# flatlamp.net
KiCad netlist of a schematic drawn in EAGLE
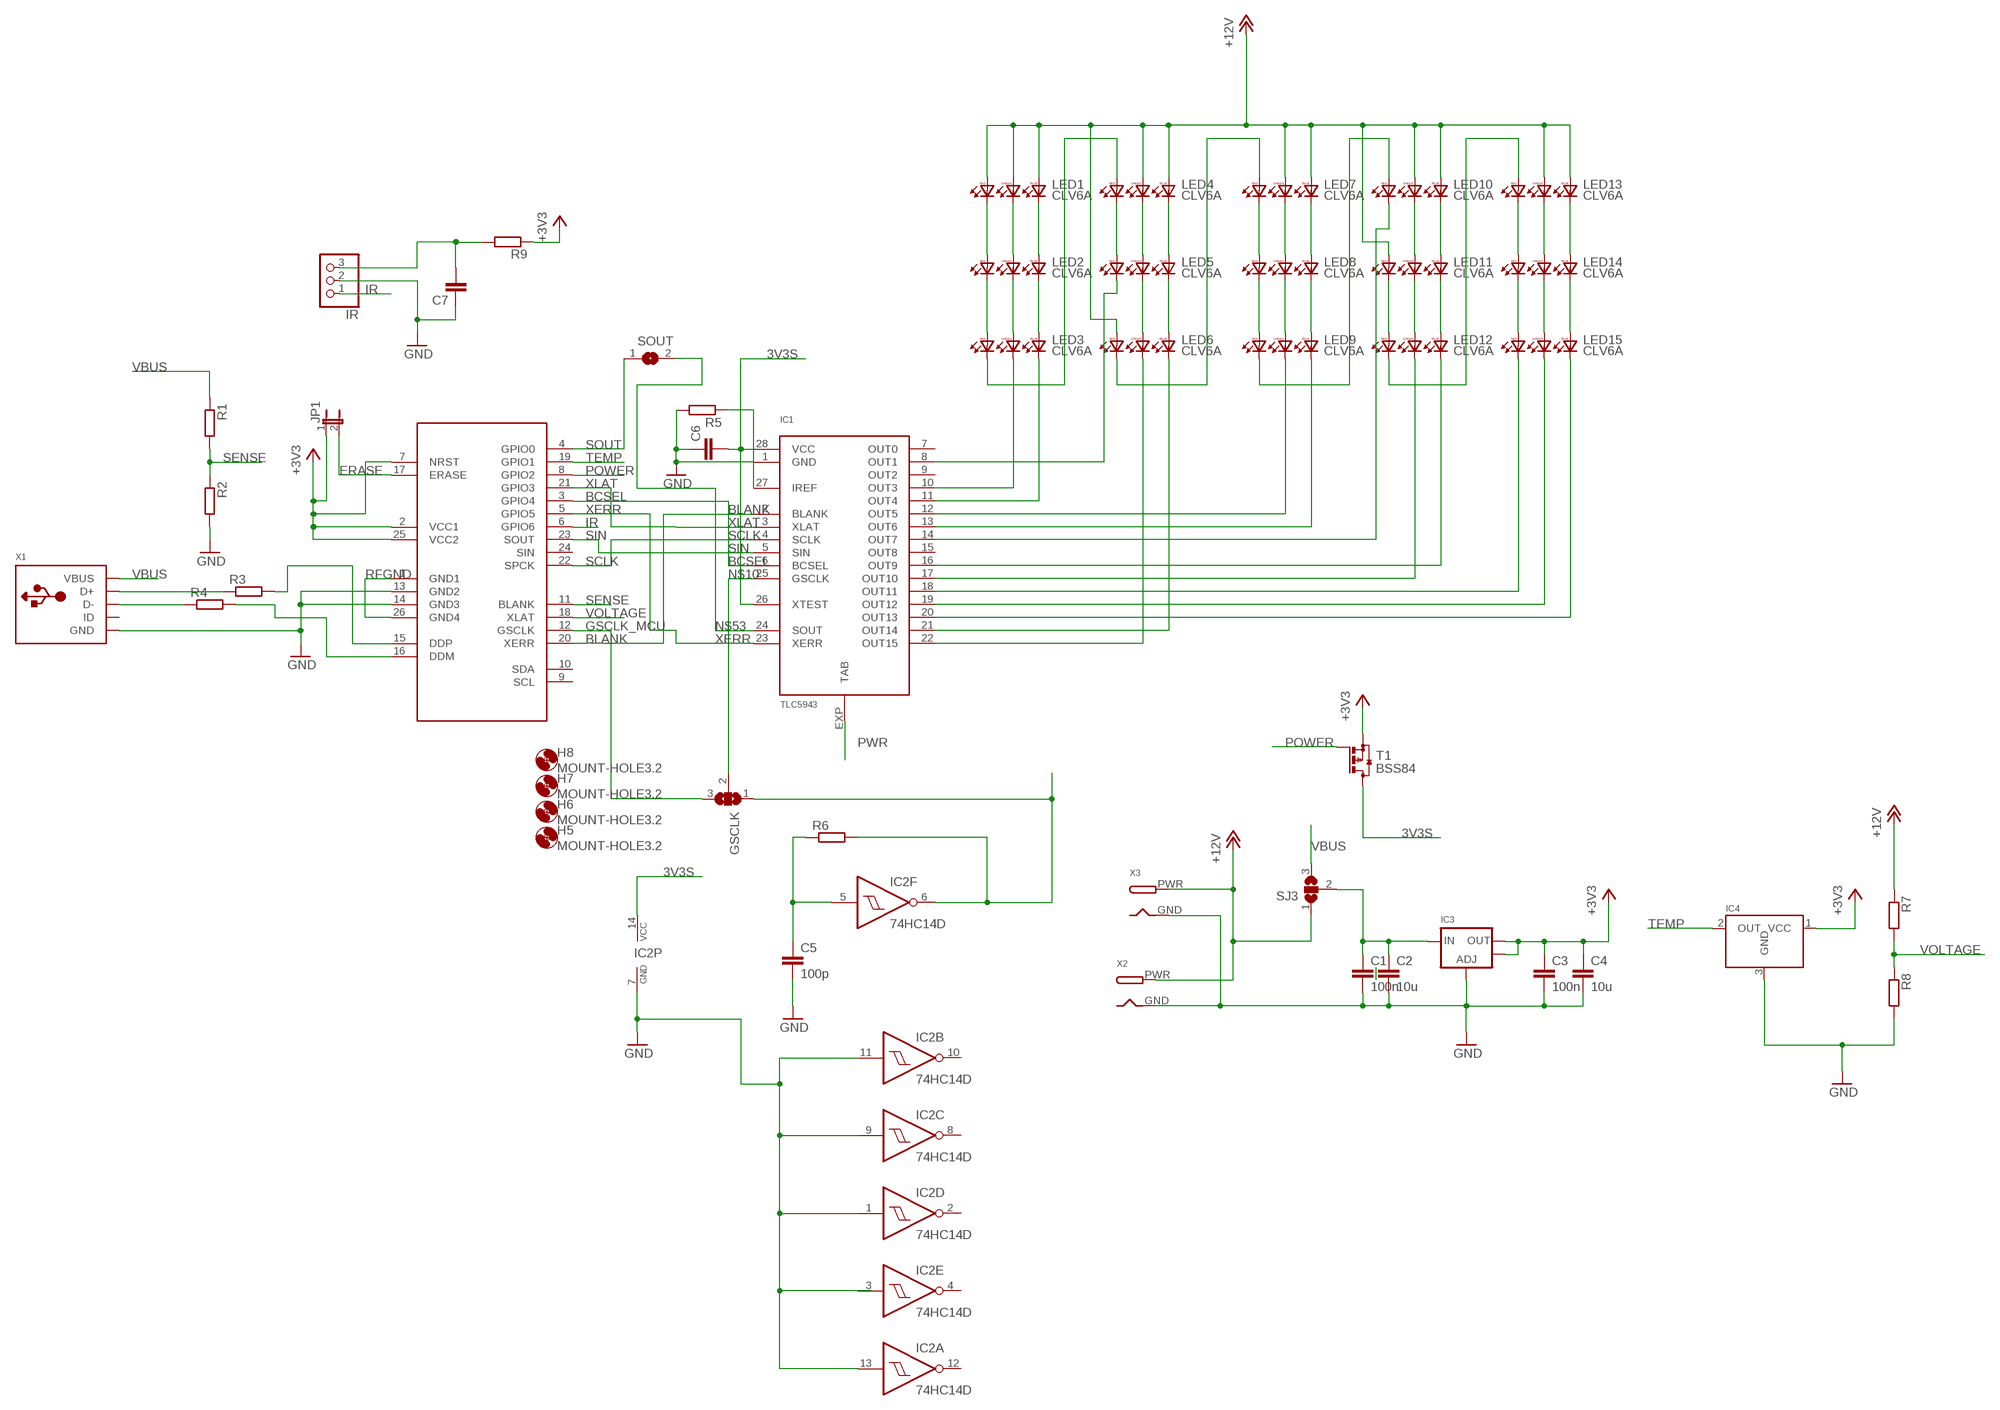
[diagram p0: schematic, sheet 1]

(export (version "E")
  (design (tool "Eeschema 10.0.6"))
  (components
    (comp (ref "C1")
      (value "100n")
      (footprint "eagle-import:C0805")
      (libsource (lib "eagle-import") (part "C-EUC0805"))
    )
    (comp (ref "C2")
      (value "10u")
      (footprint "eagle-import:C0805")
      (libsource (lib "eagle-import") (part "C-EUC0805"))
    )
    (comp (ref "C3")
      (value "100n")
      (footprint "eagle-import:C0805")
      (libsource (lib "eagle-import") (part "C-EUC0805"))
    )
    (comp (ref "C4")
      (value "10u")
      (footprint "eagle-import:C0805")
      (libsource (lib "eagle-import") (part "C-EUC0805"))
    )
    (comp (ref "C5")
      (value "100p")
      (footprint "eagle-import:C0805")
      (libsource (lib "eagle-import") (part "C-EUC0805"))
    )
    (comp (ref "C6")
      (value "C-EUC0805")
      (footprint "eagle-import:C0805")
      (libsource (lib "eagle-import") (part "C-EUC0805"))
    )
    (comp (ref "C7")
      (value "C-EUC0805")
      (footprint "eagle-import:C0805")
      (libsource (lib "eagle-import") (part "C-EUC0805"))
    )
    (comp (ref "GSCLK")
      (value "SJ2W")
      (footprint "eagle-import:SJ_2")
      (libsource (lib "eagle-import") (part "SJ2W"))
    )
    (comp (ref "H5")
      (value "MOUNT-HOLE3.2")
      (footprint "eagle-import:3,2")
      (libsource (lib "eagle-import") (part "MOUNT-HOLE3.2"))
    )
    (comp (ref "H6")
      (value "MOUNT-HOLE3.2")
      (footprint "eagle-import:3,2")
      (libsource (lib "eagle-import") (part "MOUNT-HOLE3.2"))
    )
    (comp (ref "H7")
      (value "MOUNT-HOLE3.2")
      (footprint "eagle-import:3,2")
      (libsource (lib "eagle-import") (part "MOUNT-HOLE3.2"))
    )
    (comp (ref "H8")
      (value "MOUNT-HOLE3.2")
      (footprint "eagle-import:3,2")
      (libsource (lib "eagle-import") (part "MOUNT-HOLE3.2"))
    )
    (comp (ref "IC1")
      (value "TLC5943")
      (footprint "eagle-import:HTSSOP28PWP")
      (libsource (lib "eagle-import") (part "TLC5943"))
    )
    (comp (ref "IC2")
      (value "74HC14D")
      (footprint "eagle-import:SO14")
      (libsource (lib "eagle-import") (part "7414DHC"))
    )
    (comp (ref "IC3")
      (value "LM1117SOT223-REFLOW")
      (footprint "eagle-import:SOT223-R")
      (libsource (lib "eagle-import") (part "LM1117SOT223-REFLOW"))
    )
    (comp (ref "IC4")
      (value "MCP9701T-E/TTCTREFLOW")
      (footprint "eagle-import:SOT23-R")
      (libsource (lib "eagle-import") (part "MCP9701T-E/TTCTREFLOW"))
    )
    (comp (ref "IR")
      (value "PINHD-1X3")
      (footprint "eagle-import:1X03")
      (libsource (lib "eagle-import") (part "PINHD-1X3"))
    )
    (comp (ref "JP1")
      (value "JP1E")
      (footprint "eagle-import:JP1")
      (libsource (lib "eagle-import") (part "JP1E"))
    )
    (comp (ref "LED1")
      (value "CLV6A")
      (footprint "eagle-import:PLCC6")
      (libsource (lib "eagle-import") (part "CLV6A"))
    )
    (comp (ref "LED2")
      (value "CLV6A")
      (footprint "eagle-import:PLCC6")
      (libsource (lib "eagle-import") (part "CLV6A"))
    )
    (comp (ref "LED3")
      (value "CLV6A")
      (footprint "eagle-import:PLCC6")
      (libsource (lib "eagle-import") (part "CLV6A"))
    )
    (comp (ref "LED4")
      (value "CLV6A")
      (footprint "eagle-import:PLCC6")
      (libsource (lib "eagle-import") (part "CLV6A"))
    )
    (comp (ref "LED5")
      (value "CLV6A")
      (footprint "eagle-import:PLCC6")
      (libsource (lib "eagle-import") (part "CLV6A"))
    )
    (comp (ref "LED6")
      (value "CLV6A")
      (footprint "eagle-import:PLCC6")
      (libsource (lib "eagle-import") (part "CLV6A"))
    )
    (comp (ref "LED7")
      (value "CLV6A")
      (footprint "eagle-import:PLCC6")
      (libsource (lib "eagle-import") (part "CLV6A"))
    )
    (comp (ref "LED8")
      (value "CLV6A")
      (footprint "eagle-import:PLCC6")
      (libsource (lib "eagle-import") (part "CLV6A"))
    )
    (comp (ref "LED9")
      (value "CLV6A")
      (footprint "eagle-import:PLCC6")
      (libsource (lib "eagle-import") (part "CLV6A"))
    )
    (comp (ref "LED10")
      (value "CLV6A")
      (footprint "eagle-import:PLCC6")
      (libsource (lib "eagle-import") (part "CLV6A"))
    )
    (comp (ref "LED11")
      (value "CLV6A")
      (footprint "eagle-import:PLCC6")
      (libsource (lib "eagle-import") (part "CLV6A"))
    )
    (comp (ref "LED12")
      (value "CLV6A")
      (footprint "eagle-import:PLCC6")
      (libsource (lib "eagle-import") (part "CLV6A"))
    )
    (comp (ref "LED13")
      (value "CLV6A")
      (footprint "eagle-import:PLCC6")
      (libsource (lib "eagle-import") (part "CLV6A"))
    )
    (comp (ref "LED14")
      (value "CLV6A")
      (footprint "eagle-import:PLCC6")
      (libsource (lib "eagle-import") (part "CLV6A"))
    )
    (comp (ref "LED15")
      (value "CLV6A")
      (footprint "eagle-import:PLCC6")
      (libsource (lib "eagle-import") (part "CLV6A"))
    )
    (comp (ref "R1")
      (value "R-EU_R0805")
      (footprint "eagle-import:R0805")
      (libsource (lib "eagle-import") (part "R-EU_R0805"))
    )
    (comp (ref "R2")
      (value "R-EU_R0805")
      (footprint "eagle-import:R0805")
      (libsource (lib "eagle-import") (part "R-EU_R0805"))
    )
    (comp (ref "R3")
      (value "R-EU_R0805")
      (footprint "eagle-import:R0805")
      (libsource (lib "eagle-import") (part "R-EU_R0805"))
    )
    (comp (ref "R4")
      (value "R-EU_R0805")
      (footprint "eagle-import:R0805")
      (libsource (lib "eagle-import") (part "R-EU_R0805"))
    )
    (comp (ref "R5")
      (value "R-EU_R0805")
      (footprint "eagle-import:R0805")
      (libsource (lib "eagle-import") (part "R-EU_R0805"))
    )
    (comp (ref "R6")
      (value "R-EU_R0805")
      (footprint "eagle-import:R0805")
      (libsource (lib "eagle-import") (part "R-EU_R0805"))
    )
    (comp (ref "R7")
      (value "R-EU_R0805")
      (footprint "eagle-import:R0805")
      (libsource (lib "eagle-import") (part "R-EU_R0805"))
    )
    (comp (ref "R8")
      (value "R-EU_R0805")
      (footprint "eagle-import:R0805")
      (libsource (lib "eagle-import") (part "R-EU_R0805"))
    )
    (comp (ref "R9")
      (value "R-EU_R0805")
      (footprint "eagle-import:R0805")
      (libsource (lib "eagle-import") (part "R-EU_R0805"))
    )
    (comp (ref "SJ3")
      (value "SJ2W")
      (footprint "eagle-import:SJ_2")
      (libsource (lib "eagle-import") (part "SJ2W"))
    )
    (comp (ref "SOUT")
      (value "SJ")
      (footprint "eagle-import:SJ")
      (libsource (lib "eagle-import") (part "SJ"))
    )
    (comp (ref "T1")
      (value "BSS84")
      (footprint "eagle-import:SOT23")
      (libsource (lib "eagle-import") (part "BSS84"))
    )
    (comp (ref "U$1")
      (value "RFBOARD")
      (footprint "eagle-import:RFBOARD")
      (libsource (lib "eagle-import") (part "RFBOARD"))
    )
    (comp (ref "X1")
      (value "USBMINIB")
      (footprint "eagle-import:USB-MINIB")
      (libsource (lib "eagle-import") (part "USBMINIB"))
    )
    (comp (ref "X2")
      (value "DCBARRELPTH")
      (footprint "eagle-import:DCJACK_2MM_PTH")
      (libsource (lib "eagle-import") (part "DCBARRELPTH"))
    )
    (comp (ref "X3")
      (value "DCBARRELPTH")
      (footprint "eagle-import:DCJACK_2MM_PTH")
      (libsource (lib "eagle-import") (part "DCBARRELPTH"))
    )
  )
  (nets
    (net (code "1") (name "+3V3") (class "Default")
      (node (ref "C3") (pin "1") (pinfunction "1_1") (pintype "passive"))
      (node (ref "C4") (pin "1") (pinfunction "1_1") (pintype "passive"))
      (node (ref "IC3") (pin "2") (pinfunction "OUT_2") (pintype "passive"))
      (node (ref "IC3") (pin "4") (pinfunction "OUT1_4") (pintype "passive"))
      (node (ref "IC4") (pin "1") (pinfunction "VCC_1") (pintype "power_in"))
      (node (ref "JP1") (pin "1") (pinfunction "1_1") (pintype "passive"))
      (node (ref "R9") (pin "1") (pinfunction "1_1") (pintype "passive"))
      (node (ref "T1") (pin "2") (pinfunction "S_2") (pintype "passive"))
      (node (ref "U$1") (pin "2") (pinfunction "VCC1_2") (pintype "bidirectional"))
      (node (ref "U$1") (pin "25") (pinfunction "VCC2_25") (pintype "bidirectional"))
      (node (ref "U$1") (pin "7") (pinfunction "NRST_7") (pintype "bidirectional"))
    )
    (net (code "2") (name "+12V") (class "Default")
      (node (ref "LED1") (pin "4") (pinfunction "RA_4") (pintype "passive"))
      (node (ref "LED1") (pin "5") (pinfunction "GA_5") (pintype "passive"))
      (node (ref "LED1") (pin "6") (pinfunction "BA_6") (pintype "passive"))
      (node (ref "LED10") (pin "5") (pinfunction "GA_5") (pintype "passive"))
      (node (ref "LED10") (pin "6") (pinfunction "BA_6") (pintype "passive"))
      (node (ref "LED11") (pin "4") (pinfunction "RA_4") (pintype "passive"))
      (node (ref "LED13") (pin "5") (pinfunction "GA_5") (pintype "passive"))
      (node (ref "LED13") (pin "6") (pinfunction "BA_6") (pintype "passive"))
      (node (ref "LED4") (pin "5") (pinfunction "GA_5") (pintype "passive"))
      (node (ref "LED4") (pin "6") (pinfunction "BA_6") (pintype "passive"))
      (node (ref "LED6") (pin "4") (pinfunction "RA_4") (pintype "passive"))
      (node (ref "LED7") (pin "5") (pinfunction "GA_5") (pintype "passive"))
      (node (ref "LED7") (pin "6") (pinfunction "BA_6") (pintype "passive"))
      (node (ref "R7") (pin "1") (pinfunction "1_1") (pintype "passive"))
      (node (ref "SJ3") (pin "1") (pinfunction "1_1") (pintype "passive"))
      (node (ref "X2") (pin "PWR") (pinfunction "PWR_PWR") (pintype "power_in"))
      (node (ref "X3") (pin "PWR") (pinfunction "PWR_PWR") (pintype "power_in"))
    )
    (net (code "3") (name "/3V3S") (class "Default")
      (node (ref "C6") (pin "2") (pinfunction "2_2") (pintype "passive"))
      (node (ref "IC1") (pin "26") (pinfunction "XTEST_26") (pintype "bidirectional"))
      (node (ref "IC1") (pin "28") (pinfunction "VCC_28") (pintype "bidirectional"))
      (node (ref "IC2") (pin "14") (pinfunction "VCC_14") (pintype "power_in"))
      (node (ref "T1") (pin "3") (pinfunction "D_3") (pintype "passive"))
    )
    (net (code "4") (name "/BCSEL") (class "Default")
      (node (ref "IC1") (pin "6") (pinfunction "BCSEL_6") (pintype "bidirectional"))
      (node (ref "U$1") (pin "3") (pinfunction "GPIO4_3") (pintype "bidirectional"))
    )
    (net (code "5") (name "/BLANK") (class "Default")
      (node (ref "IC1") (pin "2") (pinfunction "BLANK_2") (pintype "bidirectional"))
      (node (ref "U$1") (pin "20") (pinfunction "XERR_20") (pintype "bidirectional"))
    )
    (net (code "6") (name "/ERASE") (class "Default")
      (node (ref "JP1") (pin "2") (pinfunction "2_2") (pintype "passive"))
      (node (ref "U$1") (pin "17") (pinfunction "ERASE_17") (pintype "bidirectional"))
    )
    (net (code "7") (name "/GSCLK_MCU") (class "Default")
      (node (ref "GSCLK") (pin "3") (pinfunction "3_3") (pintype "passive"))
      (node (ref "U$1") (pin "12") (pinfunction "GSCLK_12") (pintype "bidirectional"))
    )
    (net (code "8") (name "/IR") (class "Default")
      (node (ref "IR") (pin "1") (pinfunction "1_1") (pintype "passive"))
      (node (ref "U$1") (pin "6") (pinfunction "GPIO6_6") (pintype "bidirectional"))
    )
    (net (code "9") (name "/N$10") (class "Default")
      (node (ref "GSCLK") (pin "2") (pinfunction "2_2") (pintype "passive"))
      (node (ref "IC1") (pin "25") (pinfunction "GSCLK_25") (pintype "bidirectional"))
    )
    (net (code "10") (name "/N$53") (class "Default")
      (node (ref "IC1") (pin "24") (pinfunction "SOUT_24") (pintype "bidirectional"))
      (node (ref "SOUT") (pin "2") (pinfunction "2_2") (pintype "passive"))
    )
    (net (code "11") (name "/POWER") (class "Default")
      (node (ref "T1") (pin "1") (pinfunction "G_1") (pintype "passive"))
      (node (ref "U$1") (pin "8") (pinfunction "GPIO2_8") (pintype "bidirectional"))
    )
    (net (code "12") (name "/PWR") (class "Default")
      (node (ref "IC1") (pin "EXP") (pinfunction "TAB_EXP") (pintype "bidirectional"))
    )
    (net (code "13") (name "/RFGND") (class "Default")
      (node (ref "U$1") (pin "1") (pinfunction "GND1_1") (pintype "bidirectional"))
      (node (ref "U$1") (pin "26") (pinfunction "GND4_26") (pintype "bidirectional"))
    )
    (net (code "14") (name "/SCLK") (class "Default")
      (node (ref "IC1") (pin "4") (pinfunction "SCLK_4") (pintype "bidirectional"))
      (node (ref "U$1") (pin "22") (pinfunction "SPCK_22") (pintype "bidirectional"))
    )
    (net (code "15") (name "/SENSE") (class "Default")
      (node (ref "R1") (pin "2") (pinfunction "2_2") (pintype "passive"))
      (node (ref "R2") (pin "1") (pinfunction "1_1") (pintype "passive"))
      (node (ref "U$1") (pin "11") (pinfunction "BLANK_11") (pintype "bidirectional"))
    )
    (net (code "16") (name "/SIN") (class "Default")
      (node (ref "IC1") (pin "5") (pinfunction "SIN_5") (pintype "bidirectional"))
      (node (ref "U$1") (pin "23") (pinfunction "SOUT_23") (pintype "bidirectional"))
    )
    (net (code "17") (name "/SOUT") (class "Default")
      (node (ref "SOUT") (pin "1") (pinfunction "1_1") (pintype "passive"))
      (node (ref "U$1") (pin "4") (pinfunction "GPIO0_4") (pintype "bidirectional"))
    )
    (net (code "18") (name "/TEMP") (class "Default")
      (node (ref "IC4") (pin "2") (pinfunction "OUT_2") (pintype "bidirectional"))
      (node (ref "U$1") (pin "19") (pinfunction "GPIO1_19") (pintype "bidirectional"))
    )
    (net (code "19") (name "/VBUS") (class "Default")
      (node (ref "R1") (pin "1") (pinfunction "1_1") (pintype "passive"))
      (node (ref "SJ3") (pin "3") (pinfunction "3_3") (pintype "passive"))
      (node (ref "X1") (pin "VBUS") (pinfunction "VBUS_VBUS") (pintype "power_in"))
    )
    (net (code "20") (name "/VOLTAGE") (class "Default")
      (node (ref "R7") (pin "2") (pinfunction "2_2") (pintype "passive"))
      (node (ref "R8") (pin "1") (pinfunction "1_1") (pintype "passive"))
      (node (ref "U$1") (pin "18") (pinfunction "XLAT_18") (pintype "bidirectional"))
    )
    (net (code "21") (name "/XERR") (class "Default")
      (node (ref "IC1") (pin "23") (pinfunction "XERR_23") (pintype "bidirectional"))
      (node (ref "U$1") (pin "5") (pinfunction "GPIO5_5") (pintype "bidirectional"))
    )
    (net (code "22") (name "/XLAT") (class "Default")
      (node (ref "IC1") (pin "3") (pinfunction "XLAT_3") (pintype "bidirectional"))
      (node (ref "U$1") (pin "21") (pinfunction "GPIO3_21") (pintype "bidirectional"))
    )
    (net (code "23") (name "GND") (class "Default")
      (node (ref "C1") (pin "2") (pinfunction "2_2") (pintype "passive"))
      (node (ref "C2") (pin "2") (pinfunction "2_2") (pintype "passive"))
      (node (ref "C3") (pin "2") (pinfunction "2_2") (pintype "passive"))
      (node (ref "C4") (pin "2") (pinfunction "2_2") (pintype "passive"))
      (node (ref "C5") (pin "2") (pinfunction "2_2") (pintype "passive"))
      (node (ref "C6") (pin "1") (pinfunction "1_1") (pintype "passive"))
      (node (ref "C7") (pin "1") (pinfunction "1_1") (pintype "passive"))
      (node (ref "IC1") (pin "1") (pinfunction "GND_1") (pintype "bidirectional"))
      (node (ref "IC2") (pin "1") (pinfunction "I_1") (pintype "input"))
      (node (ref "IC2") (pin "11") (pinfunction "I_11") (pintype "input"))
      (node (ref "IC2") (pin "13") (pinfunction "I_13") (pintype "input"))
      (node (ref "IC2") (pin "7") (pinfunction "GND_7") (pintype "power_in"))
      (node (ref "IC2") (pin "9") (pinfunction "I_9") (pintype "input"))
      (node (ref "IC3") (pin "1") (pinfunction "ADJ_1") (pintype "input"))
      (node (ref "IC4") (pin "3") (pinfunction "GND_3") (pintype "power_in"))
      (node (ref "IR") (pin "2") (pinfunction "2_2") (pintype "passive"))
      (node (ref "R2") (pin "2") (pinfunction "2_2") (pintype "passive"))
      (node (ref "R5") (pin "2") (pinfunction "2_2") (pintype "passive"))
      (node (ref "R8") (pin "2") (pinfunction "2_2") (pintype "passive"))
      (node (ref "U$1") (pin "13") (pinfunction "GND2_13") (pintype "bidirectional"))
      (node (ref "U$1") (pin "14") (pinfunction "GND3_14") (pintype "bidirectional"))
      (node (ref "X1") (pin "GND") (pinfunction "GND_GND") (pintype "power_in"))
      (node (ref "X2") (pin "GND") (pinfunction "GND_GND") (pintype "power_in"))
      (node (ref "X3") (pin "GND") (pinfunction "GND_GND") (pintype "power_in"))
    )
    (net (code "24") (name "Net-(C7-Pad2)") (class "Default")
      (node (ref "C7") (pin "2") (pinfunction "2_2") (pintype "passive"))
      (node (ref "IR") (pin "3") (pinfunction "3_3") (pintype "passive"))
      (node (ref "R9") (pin "2") (pinfunction "2_2") (pintype "passive"))
    )
    (net (code "25") (name "Net-(IC1-IREF)") (class "Default")
      (node (ref "IC1") (pin "27") (pinfunction "IREF_27") (pintype "bidirectional"))
      (node (ref "R5") (pin "1") (pinfunction "1_1") (pintype "passive"))
    )
    (net (code "26") (name "Net-(IC1-OUT1)") (class "Default")
      (node (ref "IC1") (pin "8") (pinfunction "OUT1_8") (pintype "bidirectional"))
      (node (ref "LED5") (pin "3") (pinfunction "RC_3") (pintype "passive"))
    )
    (net (code "27") (name "Net-(IC1-OUT3)") (class "Default")
      (node (ref "IC1") (pin "10") (pinfunction "OUT3_10") (pintype "bidirectional"))
      (node (ref "LED3") (pin "2") (pinfunction "GC_2") (pintype "passive"))
    )
    (net (code "28") (name "Net-(IC1-OUT4)") (class "Default")
      (node (ref "IC1") (pin "11") (pinfunction "OUT4_11") (pintype "bidirectional"))
      (node (ref "LED3") (pin "1") (pinfunction "BC_1") (pintype "passive"))
    )
    (net (code "29") (name "Net-(IC1-OUT5)") (class "Default")
      (node (ref "IC1") (pin "12") (pinfunction "OUT5_12") (pintype "bidirectional"))
      (node (ref "LED9") (pin "2") (pinfunction "GC_2") (pintype "passive"))
    )
    (net (code "30") (name "Net-(IC1-OUT6)") (class "Default")
      (node (ref "IC1") (pin "13") (pinfunction "OUT6_13") (pintype "bidirectional"))
      (node (ref "LED9") (pin "1") (pinfunction "BC_1") (pintype "passive"))
    )
    (net (code "31") (name "Net-(IC1-OUT7)") (class "Default")
      (node (ref "IC1") (pin "14") (pinfunction "OUT7_14") (pintype "bidirectional"))
      (node (ref "LED10") (pin "3") (pinfunction "RC_3") (pintype "passive"))
    )
    (net (code "32") (name "Net-(IC1-OUT9)") (class "Default")
      (node (ref "IC1") (pin "16") (pinfunction "OUT9_16") (pintype "bidirectional"))
      (node (ref "LED12") (pin "1") (pinfunction "BC_1") (pintype "passive"))
    )
    (net (code "33") (name "Net-(IC1-OUT10)") (class "Default")
      (node (ref "IC1") (pin "17") (pinfunction "OUT10_17") (pintype "bidirectional"))
      (node (ref "LED12") (pin "2") (pinfunction "GC_2") (pintype "passive"))
    )
    (net (code "34") (name "Net-(IC1-OUT11)") (class "Default")
      (node (ref "IC1") (pin "18") (pinfunction "OUT11_18") (pintype "bidirectional"))
      (node (ref "LED15") (pin "3") (pinfunction "RC_3") (pintype "passive"))
    )
    (net (code "35") (name "Net-(IC1-OUT12)") (class "Default")
      (node (ref "IC1") (pin "19") (pinfunction "OUT12_19") (pintype "bidirectional"))
      (node (ref "LED15") (pin "2") (pinfunction "GC_2") (pintype "passive"))
    )
    (net (code "36") (name "Net-(IC1-OUT13)") (class "Default")
      (node (ref "IC1") (pin "20") (pinfunction "OUT13_20") (pintype "bidirectional"))
      (node (ref "LED15") (pin "1") (pinfunction "BC_1") (pintype "passive"))
    )
    (net (code "37") (name "Net-(IC1-OUT14)") (class "Default")
      (node (ref "IC1") (pin "21") (pinfunction "OUT14_21") (pintype "bidirectional"))
      (node (ref "LED6") (pin "1") (pinfunction "BC_1") (pintype "passive"))
    )
    (net (code "38") (name "Net-(IC1-OUT15)") (class "Default")
      (node (ref "IC1") (pin "22") (pinfunction "OUT15_22") (pintype "bidirectional"))
      (node (ref "LED6") (pin "2") (pinfunction "GC_2") (pintype "passive"))
    )
    (net (code "39") (name "Net-(IC2F-I)") (class "Default")
      (node (ref "C5") (pin "1") (pinfunction "1_1") (pintype "passive"))
      (node (ref "IC2") (pin "5") (pinfunction "I_5") (pintype "input"))
      (node (ref "R6") (pin "1") (pinfunction "1_1") (pintype "passive"))
    )
    (net (code "40") (name "Net-(IC2F-O)") (class "Default")
      (node (ref "GSCLK") (pin "1") (pinfunction "1_1") (pintype "passive"))
      (node (ref "IC2") (pin "6") (pinfunction "O_6") (pintype "output"))
      (node (ref "R6") (pin "2") (pinfunction "2_2") (pintype "passive"))
    )
    (net (code "41") (name "Net-(IC3-IN)") (class "Default")
      (node (ref "C1") (pin "1") (pinfunction "1_1") (pintype "passive"))
      (node (ref "C2") (pin "1") (pinfunction "1_1") (pintype "passive"))
      (node (ref "IC3") (pin "3") (pinfunction "IN_3") (pintype "input"))
      (node (ref "SJ3") (pin "2") (pinfunction "2_2") (pintype "passive"))
    )
    (net (code "42") (name "Net-(LED1-BC)") (class "Default")
      (node (ref "LED1") (pin "1") (pinfunction "BC_1") (pintype "passive"))
      (node (ref "LED2") (pin "6") (pinfunction "BA_6") (pintype "passive"))
    )
    (net (code "43") (name "Net-(LED1-GC)") (class "Default")
      (node (ref "LED1") (pin "2") (pinfunction "GC_2") (pintype "passive"))
      (node (ref "LED2") (pin "5") (pinfunction "GA_5") (pintype "passive"))
    )
    (net (code "44") (name "Net-(LED1-RC)") (class "Default")
      (node (ref "LED1") (pin "3") (pinfunction "RC_3") (pintype "passive"))
      (node (ref "LED2") (pin "4") (pinfunction "RA_4") (pintype "passive"))
    )
    (net (code "45") (name "Net-(LED2-BC)") (class "Default")
      (node (ref "LED2") (pin "1") (pinfunction "BC_1") (pintype "passive"))
      (node (ref "LED3") (pin "6") (pinfunction "BA_6") (pintype "passive"))
    )
    (net (code "46") (name "Net-(LED2-GC)") (class "Default")
      (node (ref "LED2") (pin "2") (pinfunction "GC_2") (pintype "passive"))
      (node (ref "LED3") (pin "5") (pinfunction "GA_5") (pintype "passive"))
    )
    (net (code "47") (name "Net-(LED2-RC)") (class "Default")
      (node (ref "LED2") (pin "3") (pinfunction "RC_3") (pintype "passive"))
      (node (ref "LED3") (pin "4") (pinfunction "RA_4") (pintype "passive"))
    )
    (net (code "48") (name "Net-(LED3-RC)") (class "Default")
      (node (ref "LED3") (pin "3") (pinfunction "RC_3") (pintype "passive"))
      (node (ref "LED4") (pin "4") (pinfunction "RA_4") (pintype "passive"))
    )
    (net (code "49") (name "Net-(LED4-BC)") (class "Default")
      (node (ref "LED4") (pin "1") (pinfunction "BC_1") (pintype "passive"))
      (node (ref "LED5") (pin "6") (pinfunction "BA_6") (pintype "passive"))
    )
    (net (code "50") (name "Net-(LED4-GC)") (class "Default")
      (node (ref "LED4") (pin "2") (pinfunction "GC_2") (pintype "passive"))
      (node (ref "LED5") (pin "5") (pinfunction "GA_5") (pintype "passive"))
    )
    (net (code "51") (name "Net-(LED4-RC)") (class "Default")
      (node (ref "LED4") (pin "3") (pinfunction "RC_3") (pintype "passive"))
      (node (ref "LED5") (pin "4") (pinfunction "RA_4") (pintype "passive"))
    )
    (net (code "52") (name "Net-(LED5-BC)") (class "Default")
      (node (ref "LED5") (pin "1") (pinfunction "BC_1") (pintype "passive"))
      (node (ref "LED6") (pin "6") (pinfunction "BA_6") (pintype "passive"))
    )
    (net (code "53") (name "Net-(LED5-GC)") (class "Default")
      (node (ref "LED5") (pin "2") (pinfunction "GC_2") (pintype "passive"))
      (node (ref "LED6") (pin "5") (pinfunction "GA_5") (pintype "passive"))
    )
    (net (code "54") (name "Net-(LED6-RC)") (class "Default")
      (node (ref "LED6") (pin "3") (pinfunction "RC_3") (pintype "passive"))
      (node (ref "LED7") (pin "4") (pinfunction "RA_4") (pintype "passive"))
    )
    (net (code "55") (name "Net-(LED7-BC)") (class "Default")
      (node (ref "LED7") (pin "1") (pinfunction "BC_1") (pintype "passive"))
      (node (ref "LED8") (pin "6") (pinfunction "BA_6") (pintype "passive"))
    )
    (net (code "56") (name "Net-(LED7-GC)") (class "Default")
      (node (ref "LED7") (pin "2") (pinfunction "GC_2") (pintype "passive"))
      (node (ref "LED8") (pin "5") (pinfunction "GA_5") (pintype "passive"))
    )
    (net (code "57") (name "Net-(LED7-RC)") (class "Default")
      (node (ref "LED7") (pin "3") (pinfunction "RC_3") (pintype "passive"))
      (node (ref "LED8") (pin "4") (pinfunction "RA_4") (pintype "passive"))
    )
    (net (code "58") (name "Net-(LED8-BC)") (class "Default")
      (node (ref "LED8") (pin "1") (pinfunction "BC_1") (pintype "passive"))
      (node (ref "LED9") (pin "6") (pinfunction "BA_6") (pintype "passive"))
    )
    (net (code "59") (name "Net-(LED8-GC)") (class "Default")
      (node (ref "LED8") (pin "2") (pinfunction "GC_2") (pintype "passive"))
      (node (ref "LED9") (pin "5") (pinfunction "GA_5") (pintype "passive"))
    )
    (net (code "60") (name "Net-(LED8-RC)") (class "Default")
      (node (ref "LED8") (pin "3") (pinfunction "RC_3") (pintype "passive"))
      (node (ref "LED9") (pin "4") (pinfunction "RA_4") (pintype "passive"))
    )
    (net (code "61") (name "Net-(LED10-BC)") (class "Default")
      (node (ref "LED10") (pin "1") (pinfunction "BC_1") (pintype "passive"))
      (node (ref "LED11") (pin "6") (pinfunction "BA_6") (pintype "passive"))
    )
    (net (code "62") (name "Net-(LED10-GC)") (class "Default")
      (node (ref "LED10") (pin "2") (pinfunction "GC_2") (pintype "passive"))
      (node (ref "LED11") (pin "5") (pinfunction "GA_5") (pintype "passive"))
    )
    (net (code "63") (name "Net-(LED10-RA)") (class "Default")
      (node (ref "LED10") (pin "4") (pinfunction "RA_4") (pintype "passive"))
      (node (ref "LED9") (pin "3") (pinfunction "RC_3") (pintype "passive"))
    )
    (net (code "64") (name "Net-(LED11-BC)") (class "Default")
      (node (ref "LED11") (pin "1") (pinfunction "BC_1") (pintype "passive"))
      (node (ref "LED12") (pin "6") (pinfunction "BA_6") (pintype "passive"))
    )
    (net (code "65") (name "Net-(LED11-GC)") (class "Default")
      (node (ref "LED11") (pin "2") (pinfunction "GC_2") (pintype "passive"))
      (node (ref "LED12") (pin "5") (pinfunction "GA_5") (pintype "passive"))
    )
    (net (code "66") (name "Net-(LED11-RC)") (class "Default")
      (node (ref "LED11") (pin "3") (pinfunction "RC_3") (pintype "passive"))
      (node (ref "LED12") (pin "4") (pinfunction "RA_4") (pintype "passive"))
    )
    (net (code "67") (name "Net-(LED12-RC)") (class "Default")
      (node (ref "LED12") (pin "3") (pinfunction "RC_3") (pintype "passive"))
      (node (ref "LED13") (pin "4") (pinfunction "RA_4") (pintype "passive"))
    )
    (net (code "68") (name "Net-(LED13-BC)") (class "Default")
      (node (ref "LED13") (pin "1") (pinfunction "BC_1") (pintype "passive"))
      (node (ref "LED14") (pin "6") (pinfunction "BA_6") (pintype "passive"))
    )
    (net (code "69") (name "Net-(LED13-GC)") (class "Default")
      (node (ref "LED13") (pin "2") (pinfunction "GC_2") (pintype "passive"))
      (node (ref "LED14") (pin "5") (pinfunction "GA_5") (pintype "passive"))
    )
    (net (code "70") (name "Net-(LED13-RC)") (class "Default")
      (node (ref "LED13") (pin "3") (pinfunction "RC_3") (pintype "passive"))
      (node (ref "LED14") (pin "4") (pinfunction "RA_4") (pintype "passive"))
    )
    (net (code "71") (name "Net-(LED14-BC)") (class "Default")
      (node (ref "LED14") (pin "1") (pinfunction "BC_1") (pintype "passive"))
      (node (ref "LED15") (pin "6") (pinfunction "BA_6") (pintype "passive"))
    )
    (net (code "72") (name "Net-(LED14-GC)") (class "Default")
      (node (ref "LED14") (pin "2") (pinfunction "GC_2") (pintype "passive"))
      (node (ref "LED15") (pin "5") (pinfunction "GA_5") (pintype "passive"))
    )
    (net (code "73") (name "Net-(LED14-RC)") (class "Default")
      (node (ref "LED14") (pin "3") (pinfunction "RC_3") (pintype "passive"))
      (node (ref "LED15") (pin "4") (pinfunction "RA_4") (pintype "passive"))
    )
    (net (code "74") (name "Net-(R3-Pad1)") (class "Default")
      (node (ref "R3") (pin "1") (pinfunction "1_1") (pintype "passive"))
      (node (ref "X1") (pin "D+") (pinfunction "D+_D+") (pintype "bidirectional"))
    )
    (net (code "75") (name "Net-(R4-Pad1)") (class "Default")
      (node (ref "R4") (pin "1") (pinfunction "1_1") (pintype "passive"))
      (node (ref "X1") (pin "D-") (pinfunction "D-_D-") (pintype "bidirectional"))
    )
    (net (code "76") (name "Net-(U$1-DDM)") (class "Default")
      (node (ref "R4") (pin "2") (pinfunction "2_2") (pintype "passive"))
      (node (ref "U$1") (pin "16") (pinfunction "DDM_16") (pintype "bidirectional"))
    )
    (net (code "77") (name "Net-(U$1-DDP)") (class "Default")
      (node (ref "R3") (pin "2") (pinfunction "2_2") (pintype "passive"))
      (node (ref "U$1") (pin "15") (pinfunction "DDP_15") (pintype "bidirectional"))
    )
    (net (code "78") (name "unconnected-(IC1-OUT0-Pad7)") (class "Default")
      (node (ref "IC1") (pin "7") (pinfunction "OUT0_7") (pintype "bidirectional"))
    )
    (net (code "79") (name "unconnected-(IC1-OUT2-Pad9)") (class "Default")
      (node (ref "IC1") (pin "9") (pinfunction "OUT2_9") (pintype "bidirectional"))
    )
    (net (code "80") (name "unconnected-(IC1-OUT8-Pad15)") (class "Default")
      (node (ref "IC1") (pin "15") (pinfunction "OUT8_15") (pintype "bidirectional"))
    )
    (net (code "81") (name "unconnected-(IC2A-O-Pad12)") (class "Default")
      (node (ref "IC2") (pin "12") (pinfunction "O_12") (pintype "output"))
    )
    (net (code "82") (name "unconnected-(IC2B-O-Pad10)") (class "Default")
      (node (ref "IC2") (pin "10") (pinfunction "O_10") (pintype "output"))
    )
    (net (code "83") (name "unconnected-(IC2C-O-Pad8)") (class "Default")
      (node (ref "IC2") (pin "8") (pinfunction "O_8") (pintype "output"))
    )
    (net (code "84") (name "unconnected-(IC2D-O-Pad2)") (class "Default")
      (node (ref "IC2") (pin "2") (pinfunction "O_2") (pintype "output"))
    )
    (net (code "85") (name "unconnected-(IC2E-I-Pad3)") (class "Default")
      (node (ref "IC2") (pin "3") (pinfunction "I_3") (pintype "input"))
    )
    (net (code "86") (name "unconnected-(IC2E-O-Pad4)") (class "Default")
      (node (ref "IC2") (pin "4") (pinfunction "O_4") (pintype "output"))
    )
    (net (code "87") (name "unconnected-(U$1-SCL-Pad9)") (class "Default")
      (node (ref "U$1") (pin "9") (pinfunction "SCL_9") (pintype "bidirectional"))
    )
    (net (code "88") (name "unconnected-(U$1-SDA-Pad10)") (class "Default")
      (node (ref "U$1") (pin "10") (pinfunction "SDA_10") (pintype "bidirectional"))
    )
    (net (code "89") (name "unconnected-(U$1-SIN-Pad24)") (class "Default")
      (node (ref "U$1") (pin "24") (pinfunction "SIN_24") (pintype "bidirectional"))
    )
    (net (code "90") (name "unconnected-(X1-PadID)") (class "Default")
      (node (ref "X1") (pin "ID") (pinfunction "ID_ID") (pintype "bidirectional"))
    )
  )
)
